# turret1.net
KiCad netlist of a schematic drawn in Altium Designer
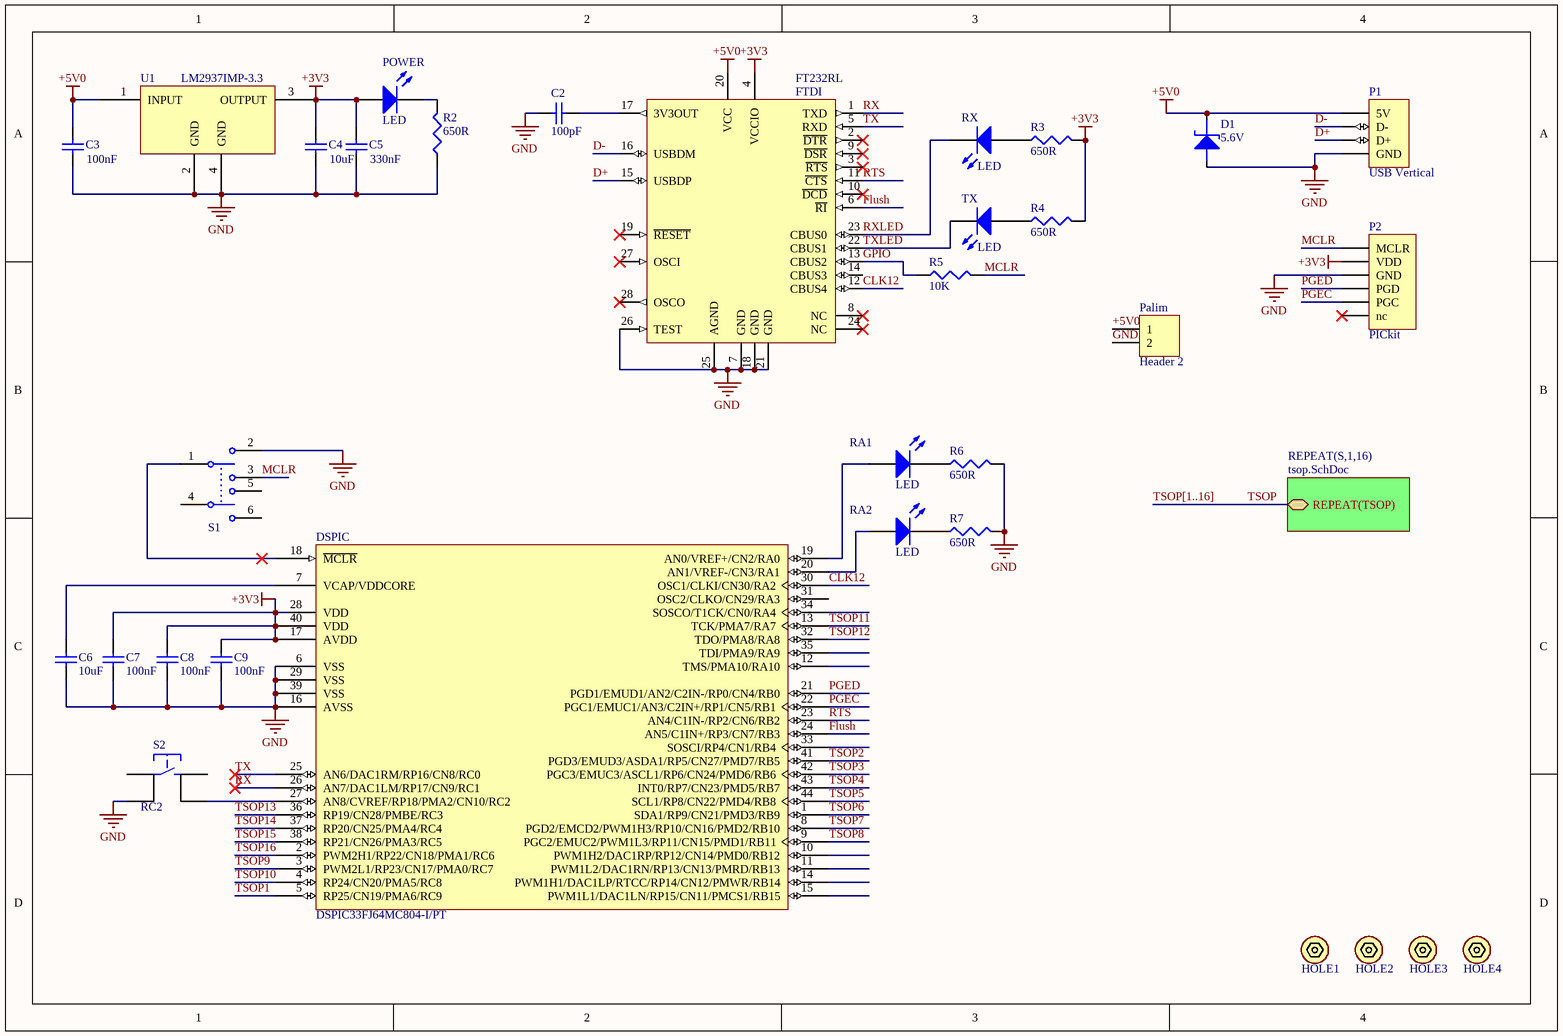
[diagram p0: turret1.SchDoc]

(export (version "E")
  (design (tool "Eeschema 10.0.6"))
  (components
    (comp (ref "C2")
      (value "100pF")
      (footprint "C0805C")
      (description "Capacitor")
      (fields (field (name "Comment") "CAP") (field (name "PUBLISHER") "Altium Limited"))
      (libsource (lib "7Robot") (part "CAP"))
    )
    (comp (ref "C3")
      (value "100nF")
      (footprint "C0805C")
      (description "Capacitor (Semiconductor SIM Model)")
      (fields (field (name "PUBLISHER") "Altium Limited"))
      (libsource (lib "Miscellaneous Devices") (part "Cap Semi"))
    )
    (comp (ref "C4")
      (value "10uF")
      (footprint "C0805C")
      (description "Capacitor (Semiconductor SIM Model)")
      (fields (field (name "PUBLISHER") "Altium Limited"))
      (libsource (lib "Miscellaneous Devices") (part "Cap Semi"))
    )
    (comp (ref "C5")
      (value "330nF")
      (footprint "C0805C")
      (description "Capacitor (Semiconductor SIM Model)")
      (fields (field (name "PUBLISHER") "Altium Limited"))
      (libsource (lib "Miscellaneous Devices") (part "Cap Semi"))
    )
    (comp (ref "C6")
      (value "10uF")
      (footprint "C0805C")
      (description "Capacitor")
      (fields (field (name "Comment") "CAP") (field (name "PUBLISHER") "Altium Limited"))
      (libsource (lib "7Robot") (part "CAP"))
    )
    (comp (ref "C7")
      (value "100nF")
      (footprint "C0805C")
      (description "Capacitor")
      (fields (field (name "Comment") "CAP") (field (name "PUBLISHER") "Altium Limited"))
      (libsource (lib "7Robot") (part "CAP"))
    )
    (comp (ref "C8")
      (value "100nF")
      (footprint "C0805C")
      (description "Capacitor")
      (fields (field (name "Comment") "CAP") (field (name "PUBLISHER") "Altium Limited"))
      (libsource (lib "7Robot") (part "CAP"))
    )
    (comp (ref "C9")
      (value "100nF")
      (footprint "C0805C")
      (description "Capacitor")
      (fields (field (name "Comment") "CAP") (field (name "PUBLISHER") "Altium Limited"))
      (libsource (lib "7Robot") (part "CAP"))
    )
    (comp (ref "D1")
      (value "5.6V")
      (footprint "DSO-C2/X1.8")
      (description "Zener Diode")
      (libsource (lib "7Robot") (part "Zener"))
    )
    (comp (ref "DSPIC")
      (value "DSPIC33FJ64MC804-I/PT")
      (footprint "TQFP-PT44_N")
      (fields (field (name "PUBLISHER") "Altium Limited"))
      (libsource (lib "7Robot") (part "DSPIC33FJ64MC804-I/PT"))
    )
    (comp (ref "FTDI")
      (value "FT232RL")
      (footprint "SSOP-28_M")
      (description "USB UART Asynchronous Serial Data Transfer Chip, SSOP-28, Tube")
      (fields (field (name "PUBLISHER") "Altium Limited"))
      (libsource (lib "7Robot") (part "FT232RL"))
    )
    (comp (ref "HOLE1")
      (value "Hole")
      (footprint "SCREW")
      (description "Mounting Hole for screws")
      (libsource (lib "7Robot") (part "Hole"))
    )
    (comp (ref "HOLE2")
      (value "Hole")
      (footprint "SCREW")
      (description "Mounting Hole for screws")
      (libsource (lib "7Robot") (part "Hole"))
    )
    (comp (ref "HOLE3")
      (value "Hole")
      (footprint "SCREW")
      (description "Mounting Hole for screws")
      (libsource (lib "7Robot") (part "Hole"))
    )
    (comp (ref "HOLE4")
      (value "Hole")
      (footprint "SCREW")
      (description "Mounting Hole for screws")
      (libsource (lib "7Robot") (part "Hole"))
    )
    (comp (ref "P1")
      (value "USB Vertical")
      (footprint "USB type B Vert")
      (description "USB Connector")
      (fields (field (name "PUBLISHER") "Altium Limited"))
      (libsource (lib "7Robot") (part "USB Con"))
    )
    (comp (ref "P2")
      (value "PICkit")
      (footprint "HDR1X6H")
      (description "Header, 6-Pin, Right Angle")
      (fields (field (name "PUBLISHER") "Altium Limited"))
      (libsource (lib "7Robot") (part "Header ICSP"))
    )
    (comp (ref "Palim")
      (value "Header 2")
      (footprint "Bornier male coude 2 voies")
      (description "Header, 2-Pin")
      (fields (field (name "PUBLISHER") "Altium Limited"))
      (libsource (lib "7Robot") (part "Header 2"))
    )
    (comp (ref "POWER")
      (value "LED")
      (footprint "LED1206G")
      (description "Typical LED")
      (fields (field (name "PUBLISHER") "Altium Limited"))
      (libsource (lib "7Robot") (part "LED"))
    )
    (comp (ref "R2")
      (value "650R")
      (footprint "C0805R")
      (description "Resistor")
      (fields (field (name "PUBLISHER") "Altium Limited"))
      (libsource (lib "Miscellaneous Devices") (part "Res3"))
    )
    (comp (ref "R3")
      (value "650R")
      (footprint "C0805R")
      (description "Resistor")
      (fields (field (name "Comment") "RES") (field (name "PUBLISHER") "Altium Limited"))
      (libsource (lib "7Robot") (part "RES"))
    )
    (comp (ref "R4")
      (value "650R")
      (footprint "C0805R")
      (description "Resistor")
      (fields (field (name "Comment") "RES") (field (name "PUBLISHER") "Altium Limited"))
      (libsource (lib "7Robot") (part "RES"))
    )
    (comp (ref "R5")
      (value "10K")
      (footprint "C0805R")
      (description "Resistor")
      (fields (field (name "Comment") "RES") (field (name "PUBLISHER") "Altium Limited"))
      (libsource (lib "7Robot") (part "RES"))
    )
    (comp (ref "R6")
      (value "650R")
      (footprint "C0805R")
      (description "Resistor")
      (fields (field (name "Comment") "RES") (field (name "PUBLISHER") "Altium Limited"))
      (libsource (lib "7Robot") (part "RES"))
    )
    (comp (ref "R7")
      (value "650R")
      (footprint "C0805R")
      (description "Resistor")
      (fields (field (name "Comment") "RES") (field (name "PUBLISHER") "Altium Limited"))
      (libsource (lib "7Robot") (part "RES"))
    )
    (comp (ref "RA1")
      (value "LED")
      (footprint "LED1206R")
      (description "Typical RED, GREEN, YELLOW, AMBER GaAs LED")
      (fields (field (name "PUBLISHER") "Altium Limited"))
      (libsource (lib "7Robot") (part "LED2"))
    )
    (comp (ref "RA2")
      (value "LED")
      (footprint "LED1206R")
      (description "Typical RED, GREEN, YELLOW, AMBER GaAs LED")
      (fields (field (name "PUBLISHER") "Altium Limited"))
      (libsource (lib "7Robot") (part "LED2"))
    )
    (comp (ref "RX")
      (value "LED")
      (footprint "LED1206Y")
      (description "Typical RED, GREEN, YELLOW, AMBER GaAs LED")
      (fields (field (name "PUBLISHER") "Altium Limited"))
      (libsource (lib "7Robot") (part "LED2"))
    )
    (comp (ref "S1")
      (value "SW-DPDT/Reset")
      (footprint "MCLSS22")
      (description "Double-Pole, Double-Throw Switch, ref MCLSS22")
      (fields (field (name "PUBLISHER") "Altium Limited"))
      (libsource (lib "7Robot") (part "SW-DPDT"))
    )
    (comp (ref "S2")
      (value "RC2")
      (footprint "SPST-NO")
      (description "Tactile Switch 7.3mm, SMD")
      (libsource (lib "7Robot") (part "SPST-NO"))
    )
    (comp (ref "TX")
      (value "LED")
      (footprint "LED1206Y")
      (description "Typical RED, GREEN, YELLOW, AMBER GaAs LED")
      (fields (field (name "PUBLISHER") "Altium Limited"))
      (libsource (lib "7Robot") (part "LED2"))
    )
    (comp (ref "U1")
      (value "LM2937IMP-3.3")
      (footprint "SOT-223")
      (description "500 mA Low Dropout Regulator")
      (libsource (lib "7Robot") (part "LM2937IMP-3.3"))
    )
  )
  (nets
    (net (code "1") (name "+3V3") (class "Default")
      (node (ref "C4") (pin "1") (pinfunction "1_1") (pintype "passive"))
      (node (ref "C5") (pin "1") (pinfunction "1_1") (pintype "passive"))
      (node (ref "C7") (pin "2") (pinfunction "2_2") (pintype "passive"))
      (node (ref "C8") (pin "2") (pinfunction "2_2") (pintype "passive"))
      (node (ref "C9") (pin "2") (pinfunction "2_2") (pintype "passive"))
      (node (ref "DSPIC") (pin "17") (pinfunction "AVDD_17") (pintype "power_in"))
      (node (ref "DSPIC") (pin "28") (pinfunction "VDD_28") (pintype "power_in"))
      (node (ref "DSPIC") (pin "40") (pinfunction "VDD_40") (pintype "power_in"))
      (node (ref "FTDI") (pin "4") (pinfunction "VCCIO_4") (pintype "power_in"))
      (node (ref "P2") (pin "2") (pinfunction "VDD_2") (pintype "passive"))
      (node (ref "POWER") (pin "1") (pinfunction "A_1") (pintype "passive"))
      (node (ref "R3") (pin "2") (pinfunction "2_2") (pintype "passive"))
      (node (ref "R4") (pin "2") (pinfunction "2_2") (pintype "passive"))
      (node (ref "U1") (pin "3") (pinfunction "OUTPUT_3") (pintype "power_in"))
    )
    (net (code "2") (name "+5V0") (class "Default")
      (node (ref "C3") (pin "1") (pinfunction "1_1") (pintype "passive"))
      (node (ref "D1") (pin "A") (pinfunction "A_A") (pintype "passive"))
      (node (ref "FTDI") (pin "20") (pinfunction "VCC_20") (pintype "power_in"))
      (node (ref "P1") (pin "1") (pinfunction "5V_1") (pintype "power_in"))
      (node (ref "Palim") (pin "1") (pinfunction "1_1") (pintype "passive"))
      (node (ref "U1") (pin "1") (pinfunction "INPUT_1") (pintype "power_in"))
    )
    (net (code "3") (name "/CLK12") (class "Default")
      (node (ref "DSPIC") (pin "30") (pinfunction "OSC1/CLKI/CN30/RA2_30") (pintype "bidirectional"))
      (node (ref "FTDI") (pin "12") (pinfunction "CBUS4_12") (pintype "bidirectional"))
    )
    (net (code "4") (name "/D+") (class "Default")
      (node (ref "FTDI") (pin "15") (pinfunction "USBDP_15") (pintype "bidirectional"))
      (node (ref "P1") (pin "3") (pinfunction "D+_3") (pintype "bidirectional"))
    )
    (net (code "5") (name "/D-") (class "Default")
      (node (ref "FTDI") (pin "16") (pinfunction "USBDM_16") (pintype "bidirectional"))
      (node (ref "P1") (pin "2") (pinfunction "D-_2") (pintype "bidirectional"))
    )
    (net (code "6") (name "/Flush") (class "Default")
      (node (ref "DSPIC") (pin "24") (pinfunction "AN5/C1IN+/RP3/CN7/RB3_24") (pintype "bidirectional"))
      (node (ref "FTDI") (pin "6") (pinfunction "~{RI}_6") (pintype "input"))
    )
    (net (code "7") (name "/GPIO") (class "Default")
      (node (ref "FTDI") (pin "13") (pinfunction "CBUS2_13") (pintype "bidirectional"))
      (node (ref "R5") (pin "1") (pinfunction "1_1") (pintype "passive"))
    )
    (net (code "8") (name "/MCLR") (class "Default")
      (node (ref "P2") (pin "1") (pinfunction "MCLR_1") (pintype "passive"))
      (node (ref "R5") (pin "2") (pinfunction "2_2") (pintype "passive"))
      (node (ref "S1") (pin "3") (pinfunction "3_3") (pintype "passive"))
    )
    (net (code "9") (name "/PGEC") (class "Default")
      (node (ref "DSPIC") (pin "22") (pinfunction "PGC1/EMUC1/AN3/C2IN+/RP1/CN5/RB1_22") (pintype "bidirectional"))
      (node (ref "P2") (pin "5") (pinfunction "PGC_5") (pintype "passive"))
    )
    (net (code "10") (name "/PGED") (class "Default")
      (node (ref "DSPIC") (pin "21") (pinfunction "PGD1/EMUD1/AN2/C2IN-/RP0/CN4/RB0_21") (pintype "bidirectional"))
      (node (ref "P2") (pin "4") (pinfunction "PGD_4") (pintype "passive"))
    )
    (net (code "11") (name "/RTS") (class "Default")
      (node (ref "DSPIC") (pin "23") (pinfunction "AN4/C1IN-/RP2/CN6/RB2_23") (pintype "bidirectional"))
      (node (ref "FTDI") (pin "11") (pinfunction "~{CTS}_11") (pintype "input"))
    )
    (net (code "12") (name "/RX") (class "Default")
      (node (ref "DSPIC") (pin "26") (pinfunction "AN7/DAC1LM/RP17/CN9/RC1_26") (pintype "bidirectional"))
      (node (ref "FTDI") (pin "1") (pinfunction "TXD_1") (pintype "output"))
    )
    (net (code "13") (name "/RXLED") (class "Default")
      (node (ref "FTDI") (pin "23") (pinfunction "CBUS0_23") (pintype "bidirectional"))
      (node (ref "RX") (pin "2") (pinfunction "K_2") (pintype "passive"))
    )
    (net (code "15") (name "/TSOP1") (class "Default")
      (node (ref "DSPIC") (pin "5") (pinfunction "RP25/CN19/PMA6/RC9_5") (pintype "bidirectional"))
    )
    (net (code "16") (name "/TSOP2") (class "Default")
      (node (ref "DSPIC") (pin "41") (pinfunction "PGD3/EMUD3/ASDA1/RP5/CN27/PMD7/RB5_41") (pintype "bidirectional"))
    )
    (net (code "17") (name "/TSOP3") (class "Default")
      (node (ref "DSPIC") (pin "42") (pinfunction "PGC3/EMUC3/ASCL1/RP6/CN24/PMD6/RB6_42") (pintype "bidirectional"))
    )
    (net (code "18") (name "/TSOP4") (class "Default")
      (node (ref "DSPIC") (pin "43") (pinfunction "INT0/RP7/CN23/PMD5/RB7_43") (pintype "bidirectional"))
    )
    (net (code "19") (name "/TSOP5") (class "Default")
      (node (ref "DSPIC") (pin "44") (pinfunction "SCL1/RP8/CN22/PMD4/RB8_44") (pintype "bidirectional"))
    )
    (net (code "20") (name "/TSOP6") (class "Default")
      (node (ref "DSPIC") (pin "1") (pinfunction "SDA1/RP9/CN21/PMD3/RB9_1") (pintype "bidirectional"))
    )
    (net (code "21") (name "/TSOP7") (class "Default")
      (node (ref "DSPIC") (pin "8") (pinfunction "PGD2/EMCD2/PWM1H3/RP10/CN16/PMD2/RB10_8") (pintype "bidirectional"))
    )
    (net (code "22") (name "/TSOP8") (class "Default")
      (node (ref "DSPIC") (pin "9") (pinfunction "PGC2/EMUC2/PWM1L3/RP11/CN15/PMD1/RB11_9") (pintype "bidirectional"))
    )
    (net (code "23") (name "/TSOP9") (class "Default")
      (node (ref "DSPIC") (pin "3") (pinfunction "PWM2L1/RP23/CN17/PMA0/RC7_3") (pintype "bidirectional"))
    )
    (net (code "24") (name "/TSOP10") (class "Default")
      (node (ref "DSPIC") (pin "4") (pinfunction "RP24/CN20/PMA5/RC8_4") (pintype "bidirectional"))
    )
    (net (code "25") (name "/TSOP11") (class "Default")
      (node (ref "DSPIC") (pin "13") (pinfunction "TCK/PMA7/RA7_13") (pintype "bidirectional"))
    )
    (net (code "26") (name "/TSOP12") (class "Default")
      (node (ref "DSPIC") (pin "32") (pinfunction "TDO/PMA8/RA8_32") (pintype "bidirectional"))
    )
    (net (code "27") (name "/TSOP13") (class "Default")
      (node (ref "DSPIC") (pin "36") (pinfunction "RP19/CN28/PMBE/RC3_36") (pintype "bidirectional"))
    )
    (net (code "28") (name "/TSOP14") (class "Default")
      (node (ref "DSPIC") (pin "37") (pinfunction "RP20/CN25/PMA4/RC4_37") (pintype "bidirectional"))
    )
    (net (code "29") (name "/TSOP15") (class "Default")
      (node (ref "DSPIC") (pin "38") (pinfunction "RP21/CN26/PMA3/RC5_38") (pintype "bidirectional"))
    )
    (net (code "30") (name "/TSOP16") (class "Default")
      (node (ref "DSPIC") (pin "2") (pinfunction "PWM2H1/RP22/CN18/PMA1/RC6_2") (pintype "bidirectional"))
    )
    (net (code "32") (name "/TX") (class "Default")
      (node (ref "DSPIC") (pin "25") (pinfunction "AN6/DAC1RM/RP16/CN8/RC0_25") (pintype "bidirectional"))
      (node (ref "FTDI") (pin "5") (pinfunction "RXD_5") (pintype "input"))
    )
    (net (code "33") (name "/TXLED") (class "Default")
      (node (ref "FTDI") (pin "22") (pinfunction "CBUS1_22") (pintype "bidirectional"))
      (node (ref "TX") (pin "2") (pinfunction "K_2") (pintype "passive"))
    )
    (net (code "34") (name "GND") (class "Default")
      (node (ref "C2") (pin "2") (pinfunction "2_2") (pintype "passive"))
      (node (ref "C3") (pin "2") (pinfunction "2_2") (pintype "passive"))
      (node (ref "C4") (pin "2") (pinfunction "2_2") (pintype "passive"))
      (node (ref "C5") (pin "2") (pinfunction "2_2") (pintype "passive"))
      (node (ref "C6") (pin "1") (pinfunction "1_1") (pintype "passive"))
      (node (ref "C7") (pin "1") (pinfunction "1_1") (pintype "passive"))
      (node (ref "C8") (pin "1") (pinfunction "1_1") (pintype "passive"))
      (node (ref "C9") (pin "1") (pinfunction "1_1") (pintype "passive"))
      (node (ref "D1") (pin "K") (pinfunction "K_K") (pintype "passive"))
      (node (ref "DSPIC") (pin "16") (pinfunction "AVSS_16") (pintype "power_in"))
      (node (ref "DSPIC") (pin "29") (pinfunction "VSS_29") (pintype "power_in"))
      (node (ref "DSPIC") (pin "39") (pinfunction "VSS_39") (pintype "power_in"))
      (node (ref "DSPIC") (pin "6") (pinfunction "VSS_6") (pintype "power_in"))
      (node (ref "FTDI") (pin "18") (pinfunction "GND_18") (pintype "power_in"))
      (node (ref "FTDI") (pin "21") (pinfunction "GND_21") (pintype "power_in"))
      (node (ref "FTDI") (pin "25") (pinfunction "AGND_25") (pintype "power_in"))
      (node (ref "FTDI") (pin "26") (pinfunction "TEST_26") (pintype "input"))
      (node (ref "FTDI") (pin "7") (pinfunction "GND_7") (pintype "power_in"))
      (node (ref "P1") (pin "4") (pinfunction "GND_4") (pintype "power_in"))
      (node (ref "P2") (pin "3") (pinfunction "GND_3") (pintype "passive"))
      (node (ref "Palim") (pin "2") (pinfunction "2_2") (pintype "passive"))
      (node (ref "R2") (pin "1") (pinfunction "1_1") (pintype "passive"))
      (node (ref "R6") (pin "2") (pinfunction "2_2") (pintype "passive"))
      (node (ref "R7") (pin "2") (pinfunction "2_2") (pintype "passive"))
      (node (ref "S1") (pin "2") (pinfunction "2_2") (pintype "passive"))
      (node (ref "S2") (pin "2") (pintype "passive"))
      (node (ref "U1") (pin "2") (pinfunction "GND_2") (pintype "power_in"))
      (node (ref "U1") (pin "4") (pinfunction "GND_4") (pintype "power_in"))
    )
    (net (code "35") (name "Net-(DSPIC-AN0{slash}VREF+{slash}CN2{slash}RA0)") (class "Default")
      (node (ref "DSPIC") (pin "19") (pinfunction "AN0/VREF+/CN2/RA0_19") (pintype "bidirectional"))
      (node (ref "RA1") (pin "1") (pinfunction "A_1") (pintype "passive"))
    )
    (net (code "36") (name "Net-(DSPIC-AN1{slash}VREF-{slash}CN3{slash}RA1)") (class "Default")
      (node (ref "DSPIC") (pin "20") (pinfunction "AN1/VREF-/CN3/RA1_20") (pintype "bidirectional"))
      (node (ref "RA2") (pin "1") (pinfunction "A_1") (pintype "passive"))
    )
    (net (code "37") (name "Net-(DSPIC-AN8{slash}CVREF{slash}RP18{slash}PMA2{slash}CN10{slash}RC2)") (class "Default")
      (node (ref "DSPIC") (pin "27") (pinfunction "AN8/CVREF/RP18/PMA2/CN10/RC2_27") (pintype "bidirectional"))
      (node (ref "S2") (pin "3") (pintype "passive"))
    )
    (net (code "38") (name "Net-(DSPIC-VCAP{slash}VDDCORE)") (class "Default")
      (node (ref "C6") (pin "2") (pinfunction "2_2") (pintype "passive"))
      (node (ref "DSPIC") (pin "7") (pinfunction "VCAP/VDDCORE_7") (pintype "power_in"))
    )
    (net (code "39") (name "Net-(DSPIC-~{MCLR})") (class "Default")
      (node (ref "DSPIC") (pin "18") (pinfunction "~{MCLR}_18") (pintype "input"))
      (node (ref "S1") (pin "1") (pinfunction "1_1") (pintype "passive"))
    )
    (net (code "40") (name "Net-(FTDI-3V3OUT)") (class "Default")
      (node (ref "C2") (pin "1") (pinfunction "1_1") (pintype "passive"))
      (node (ref "FTDI") (pin "17") (pinfunction "3V3OUT_17") (pintype "output"))
    )
    (net (code "41") (name "Net-(POWER-K)") (class "Default")
      (node (ref "POWER") (pin "2") (pinfunction "K_2") (pintype "passive"))
      (node (ref "R2") (pin "2") (pinfunction "2_2") (pintype "passive"))
    )
    (net (code "42") (name "Net-(RA1-K)") (class "Default")
      (node (ref "R6") (pin "1") (pinfunction "1_1") (pintype "passive"))
      (node (ref "RA1") (pin "2") (pinfunction "K_2") (pintype "passive"))
    )
    (net (code "43") (name "Net-(RA2-K)") (class "Default")
      (node (ref "R7") (pin "1") (pinfunction "1_1") (pintype "passive"))
      (node (ref "RA2") (pin "2") (pinfunction "K_2") (pintype "passive"))
    )
    (net (code "44") (name "Net-(RX-A)") (class "Default")
      (node (ref "R3") (pin "1") (pinfunction "1_1") (pintype "passive"))
      (node (ref "RX") (pin "1") (pinfunction "A_1") (pintype "passive"))
    )
    (net (code "45") (name "Net-(TX-A)") (class "Default")
      (node (ref "R4") (pin "1") (pinfunction "1_1") (pintype "passive"))
      (node (ref "TX") (pin "1") (pinfunction "A_1") (pintype "passive"))
    )
    (net (code "46") (name "unconnected-(DSPIC-OSC2{slash}CLKO{slash}CN29{slash}RA3-Pad31)") (class "Default")
      (node (ref "DSPIC") (pin "31") (pinfunction "OSC2/CLKO/CN29/RA3_31") (pintype "bidirectional"))
    )
    (net (code "47") (name "unconnected-(DSPIC-PWM1H1{slash}DAC1LP{slash}RTCC{slash}RP14{slash}CN12{slash}PMWR{slash}RB14-Pad14)") (class "Default")
      (node (ref "DSPIC") (pin "14") (pinfunction "PWM1H1/DAC1LP/RTCC/RP14/CN12/PMWR/RB14_14") (pintype "bidirectional"))
    )
    (net (code "48") (name "unconnected-(DSPIC-PWM1H2{slash}DAC1RP{slash}RP12{slash}CN14{slash}PMD0{slash}RB12-Pad10)") (class "Default")
      (node (ref "DSPIC") (pin "10") (pinfunction "PWM1H2/DAC1RP/RP12/CN14/PMD0/RB12_10") (pintype "bidirectional"))
    )
    (net (code "49") (name "unconnected-(DSPIC-PWM1L1{slash}DAC1LN{slash}RP15{slash}CN11{slash}PMCS1{slash}RB15-Pad15)") (class "Default")
      (node (ref "DSPIC") (pin "15") (pinfunction "PWM1L1/DAC1LN/RP15/CN11/PMCS1/RB15_15") (pintype "bidirectional"))
    )
    (net (code "50") (name "unconnected-(DSPIC-PWM1L2{slash}DAC1RN{slash}RP13{slash}CN13{slash}PMRD{slash}RB13-Pad11)") (class "Default")
      (node (ref "DSPIC") (pin "11") (pinfunction "PWM1L2/DAC1RN/RP13/CN13/PMRD/RB13_11") (pintype "bidirectional"))
    )
    (net (code "51") (name "unconnected-(DSPIC-SOSCI{slash}RP4{slash}CN1{slash}RB4-Pad33)") (class "Default")
      (node (ref "DSPIC") (pin "33") (pinfunction "SOSCI/RP4/CN1/RB4_33") (pintype "bidirectional"))
    )
    (net (code "52") (name "unconnected-(DSPIC-SOSCO{slash}T1CK{slash}CN0{slash}RA4-Pad34)") (class "Default")
      (node (ref "DSPIC") (pin "34") (pinfunction "SOSCO/T1CK/CN0/RA4_34") (pintype "bidirectional"))
    )
    (net (code "53") (name "unconnected-(DSPIC-TDI{slash}PMA9{slash}RA9-Pad35)") (class "Default")
      (node (ref "DSPIC") (pin "35") (pinfunction "TDI/PMA9/RA9_35") (pintype "bidirectional"))
    )
    (net (code "54") (name "unconnected-(DSPIC-TMS{slash}PMA10{slash}RA10-Pad12)") (class "Default")
      (node (ref "DSPIC") (pin "12") (pinfunction "TMS/PMA10/RA10_12") (pintype "bidirectional"))
    )
    (net (code "55") (name "unconnected-(FTDI-CBUS3-Pad14)") (class "Default")
      (node (ref "FTDI") (pin "14") (pinfunction "CBUS3_14") (pintype "bidirectional"))
    )
    (net (code "56") (name "unconnected-(FTDI-NC-Pad8)") (class "Default")
      (node (ref "FTDI") (pin "8") (pinfunction "NC_8") (pintype "passive+no_connect"))
    )
    (net (code "57") (name "unconnected-(FTDI-NC-Pad24)") (class "Default")
      (node (ref "FTDI") (pin "24") (pinfunction "NC_24") (pintype "passive+no_connect"))
    )
    (net (code "58") (name "unconnected-(FTDI-OSCI-Pad27)") (class "Default")
      (node (ref "FTDI") (pin "27") (pinfunction "OSCI_27") (pintype "input+no_connect"))
    )
    (net (code "59") (name "unconnected-(FTDI-OSCO-Pad28)") (class "Default")
      (node (ref "FTDI") (pin "28") (pinfunction "OSCO_28") (pintype "output+no_connect"))
    )
    (net (code "60") (name "unconnected-(FTDI-~{DCD}-Pad10)") (class "Default")
      (node (ref "FTDI") (pin "10") (pinfunction "~{DCD}_10") (pintype "input+no_connect"))
    )
    (net (code "61") (name "unconnected-(FTDI-~{DSR}-Pad9)") (class "Default")
      (node (ref "FTDI") (pin "9") (pinfunction "~{DSR}_9") (pintype "input+no_connect"))
    )
    (net (code "62") (name "unconnected-(FTDI-~{DTR}-Pad2)") (class "Default")
      (node (ref "FTDI") (pin "2") (pinfunction "~{DTR}_2") (pintype "output+no_connect"))
    )
    (net (code "63") (name "unconnected-(FTDI-~{RESET}-Pad19)") (class "Default")
      (node (ref "FTDI") (pin "19") (pinfunction "~{RESET}_19") (pintype "input+no_connect"))
    )
    (net (code "64") (name "unconnected-(FTDI-~{RTS}-Pad3)") (class "Default")
      (node (ref "FTDI") (pin "3") (pinfunction "~{RTS}_3") (pintype "output+no_connect"))
    )
    (net (code "65") (name "unconnected-(HOLE1-Hole-Pad1)") (class "Default")
      (node (ref "HOLE1") (pin "1") (pinfunction "Hole_1") (pintype "passive"))
    )
    (net (code "66") (name "unconnected-(HOLE2-Hole-Pad1)") (class "Default")
      (node (ref "HOLE2") (pin "1") (pinfunction "Hole_1") (pintype "passive"))
    )
    (net (code "67") (name "unconnected-(HOLE3-Hole-Pad1)") (class "Default")
      (node (ref "HOLE3") (pin "1") (pinfunction "Hole_1") (pintype "passive"))
    )
    (net (code "68") (name "unconnected-(HOLE4-Hole-Pad1)") (class "Default")
      (node (ref "HOLE4") (pin "1") (pinfunction "Hole_1") (pintype "passive"))
    )
    (net (code "69") (name "unconnected-(P2-nc-Pad6)") (class "Default")
      (node (ref "P2") (pin "6") (pinfunction "nc_6") (pintype "passive+no_connect"))
    )
    (net (code "70") (name "unconnected-(S1-Pad4)") (class "Default")
      (node (ref "S1") (pin "4") (pinfunction "4_4") (pintype "passive"))
    )
    (net (code "71") (name "unconnected-(S1-Pad5)") (class "Default")
      (node (ref "S1") (pin "5") (pinfunction "5_5") (pintype "passive"))
    )
    (net (code "72") (name "unconnected-(S1-Pad6)") (class "Default")
      (node (ref "S1") (pin "6") (pinfunction "6_6") (pintype "passive"))
    )
    (net (code "73") (name "unconnected-(S2-Pad1)") (class "Default")
      (node (ref "S2") (pin "1") (pintype "passive"))
    )
    (net (code "74") (name "unconnected-(S2-Pad4)") (class "Default")
      (node (ref "S2") (pin "4") (pintype "passive"))
    )
  )
)
